# pump_system.net
KiCad netlist of a schematic drawn in EasyEDA
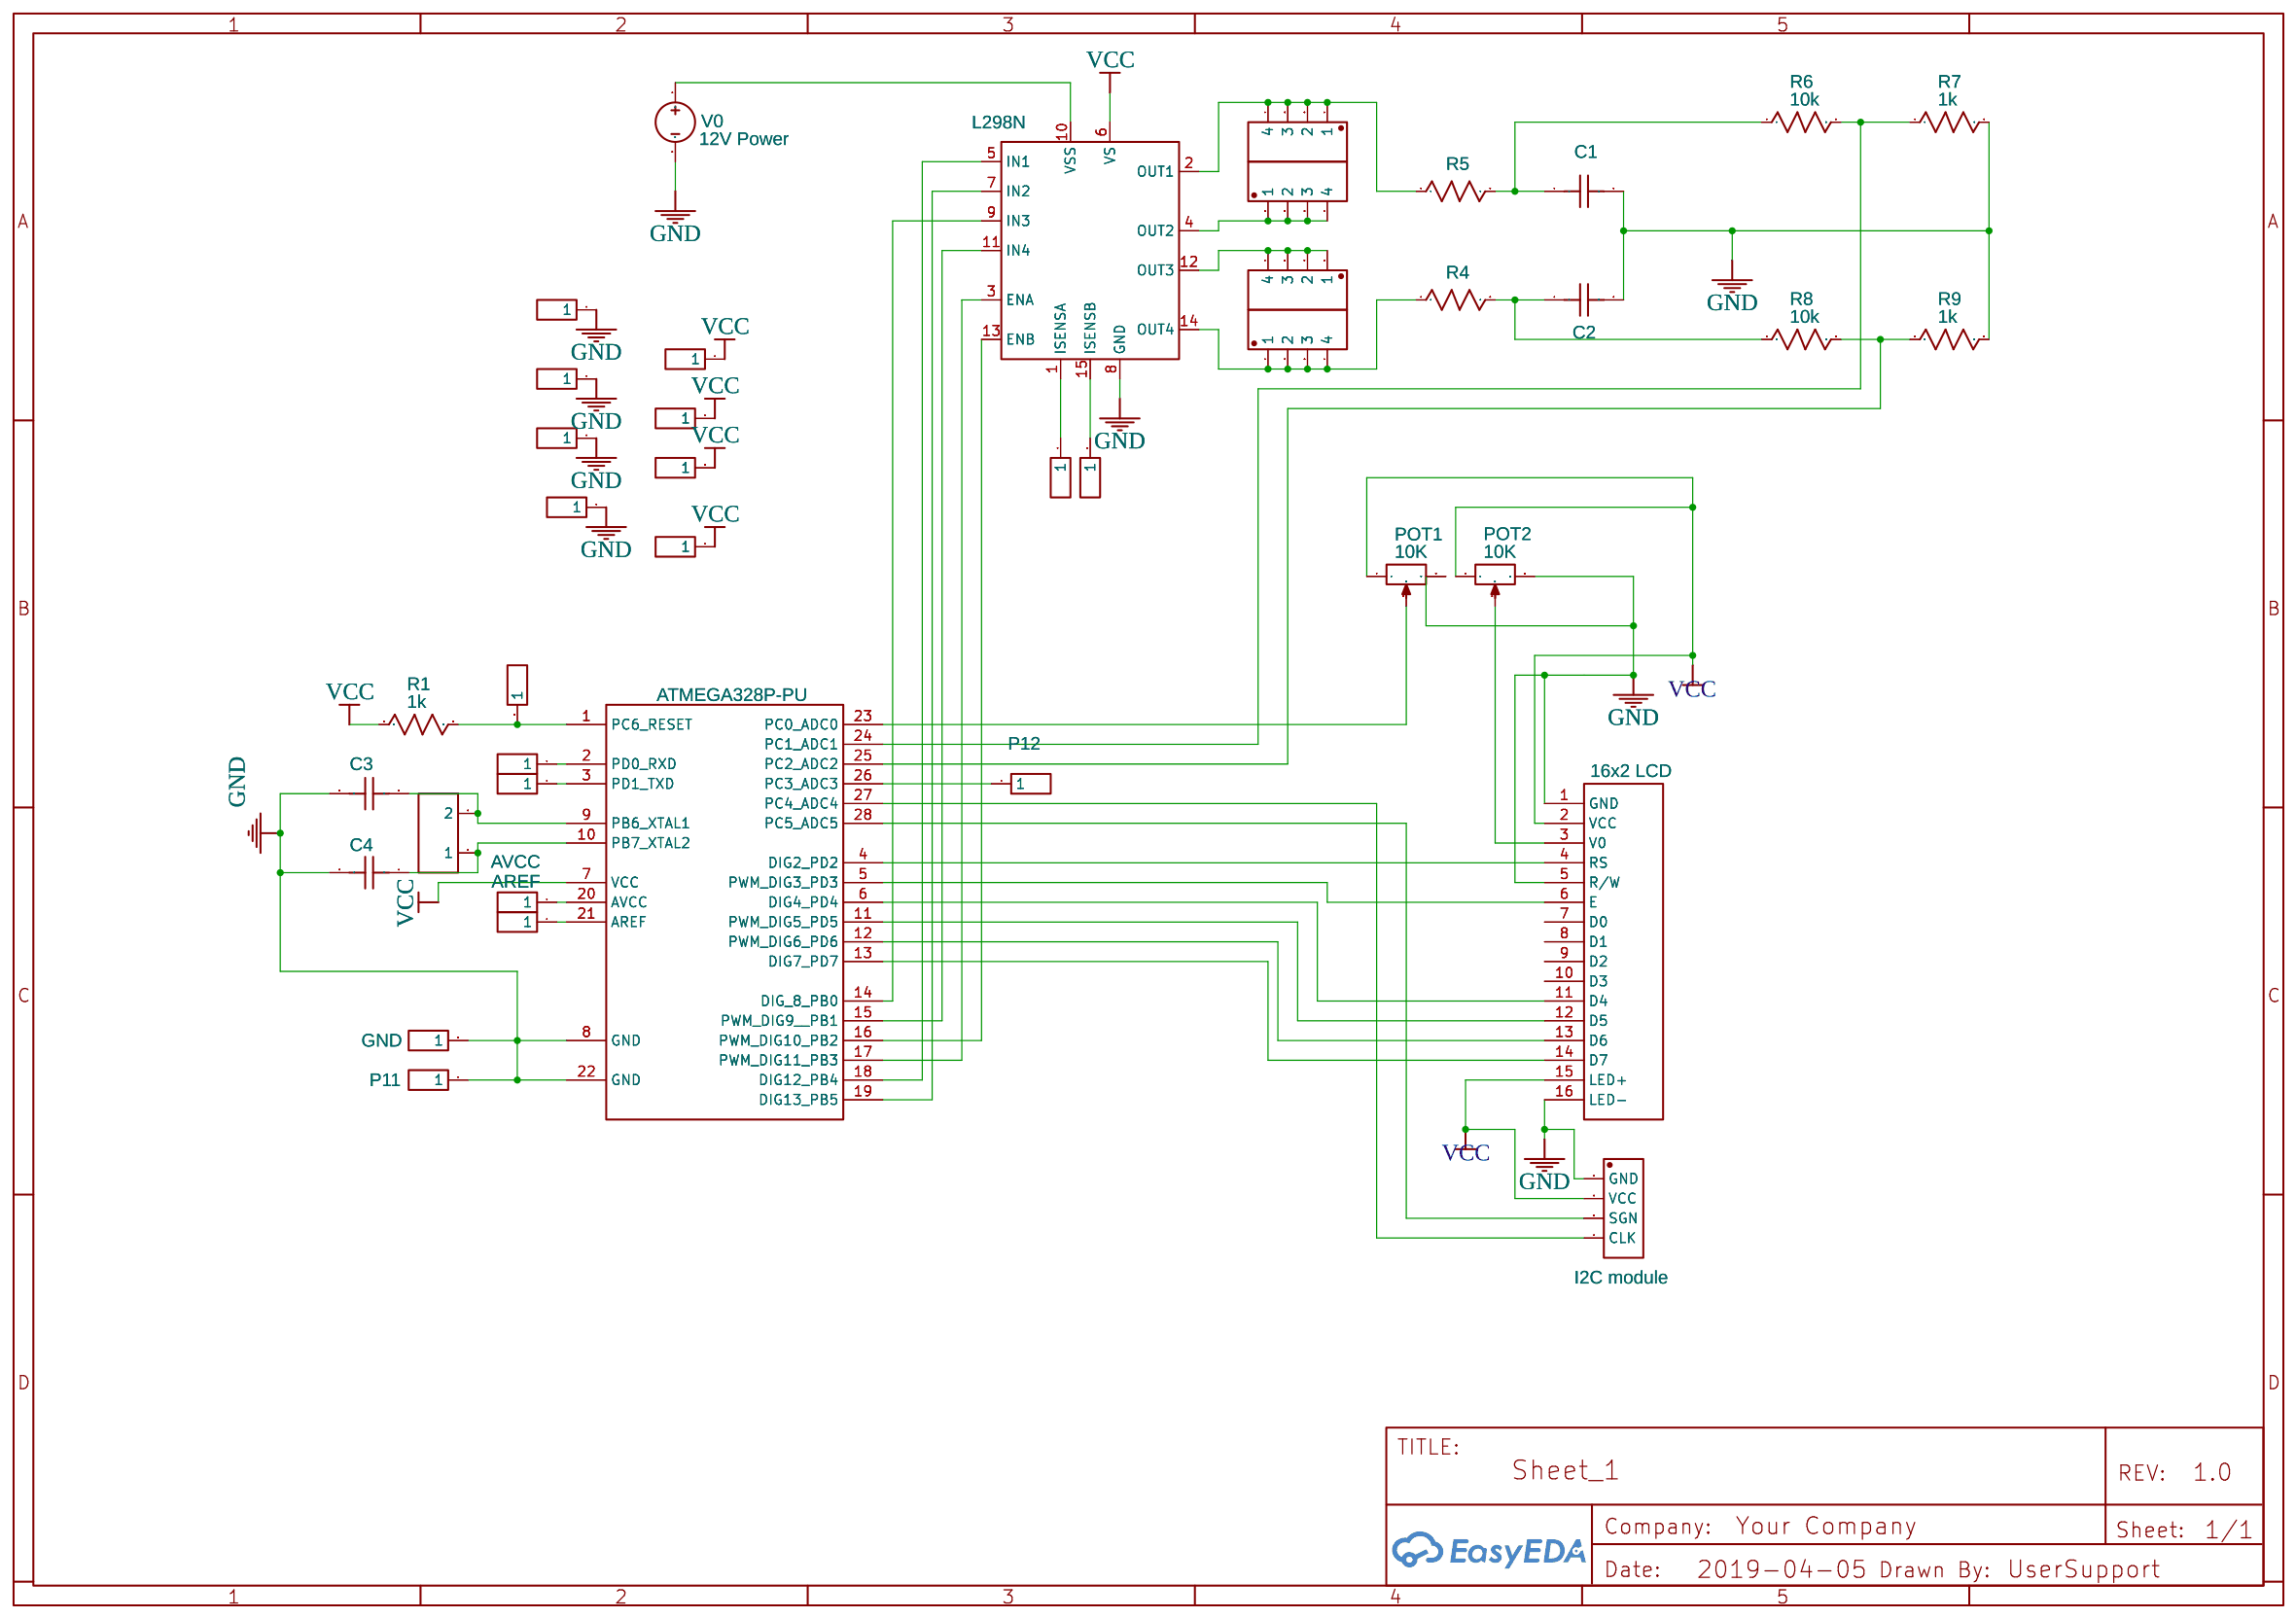
[diagram p0: schematic sheet]

(export (version "E")
  (design (tool "Eeschema 10.0.6"))
  (components
    (comp (ref "AREF")
      (value "Header-Male-2.54_1x1")
      (fields (field (name "BOM_Supplier Part") "C81276"))
      (libsource (lib "") (part "Unknown_260_460"))
    )
    (comp (ref "AVCC")
      (value "Header-Male-2.54_1x1")
      (fields (field (name "BOM_Supplier Part") "C81276"))
      (libsource (lib "") (part "Unknown_260_450"))
    )
    (comp (ref "C1")
      (value "1u")
      (fields (field (name "BOM_Manufacturer Part") "?"))
      (libsource (lib "") (part "Cap_RAD-0.1_US"))
    )
    (comp (ref "C2")
      (value "1u")
      (fields (field (name "BOM_Manufacturer Part") "?"))
      (libsource (lib "") (part "Cap_RAD-0.1_US"))
    )
    (comp (ref "C3")
      (value "1u")
      (fields (field (name "BOM_Manufacturer Part") "?"))
      (libsource (lib "") (part "Cap_RAD-0.1_US_1"))
    )
    (comp (ref "C4")
      (value "1u")
      (fields (field (name "BOM_Manufacturer Part") "?"))
      (libsource (lib "") (part "Cap_RAD-0.1_US_1"))
    )
    (comp (ref "GND")
      (value "Header-Male-2.54_1x1")
      (fields (field (name "BOM_Supplier Part") "C81276"))
      (libsource (lib "") (part "Unknown_215_520"))
    )
    (comp (ref "H1")
      (value "I2C module")
      (fields
        (field (name "BOM_Manufacturer Part") "210S-1*4P L=11.6MMGold-plated black")
        (field (name "BOM_Supplier Part") "C124378")
      )
      (libsource (lib "") (part "Unknown_810_605"))
    )
    (comp (ref "H2")
      (value "Header-Male-2.54_1x4")
      (fields
        (field (name "BOM_Manufacturer Part") "210S-1*4P L=11.6MMGold-plated black")
        (field (name "BOM_Supplier Part") "C124378")
      )
      (libsource (lib "") (part "Unknown_650_90"))
    )
    (comp (ref "H3")
      (value "Header-Male-2.54_1x4")
      (fields
        (field (name "BOM_Manufacturer Part") "210S-1*4P L=11.6MMGold-plated black")
        (field (name "BOM_Supplier Part") "C124378")
      )
      (libsource (lib "") (part "Unknown_650_60"))
    )
    (comp (ref "H4")
      (value "Header-Male-2.54_1x4")
      (fields
        (field (name "BOM_Manufacturer Part") "210S-1*4P L=11.6MMGold-plated black")
        (field (name "BOM_Supplier Part") "C124378")
      )
      (libsource (lib "") (part "Unknown_650_165"))
    )
    (comp (ref "H5")
      (value "Header-Male-2.54_1x4")
      (fields
        (field (name "BOM_Manufacturer Part") "210S-1*4P L=11.6MMGold-plated black")
        (field (name "BOM_Supplier Part") "C124378")
      )
      (libsource (lib "") (part "Unknown_650_135"))
    )
    (comp (ref "H6")
      (value "Header-Male-2.54_1x2")
      (fields (field (name "BOM_Manufacturer Part") "826629-2") (field (name "BOM_Supplier Part") "C86471"))
      (libsource (lib "") (part "Unknown_220_415"))
    )
    (comp (ref "L298N")
      (value "L298N Personal")
      (fields (field (name "BOM_Manufacturer Part") "L298N") (field (name "BOM_Supplier Part") "C19922"))
      (libsource (lib "") (part "Unknown_545_120"))
    )
    (comp (ref "P1")
      (value "Header-Male-2.54_1x1")
      (fields (field (name "BOM_Supplier Part") "C81276"))
      (libsource (lib "") (part "Unknown_280_150"))
    )
    (comp (ref "P2")
      (value "Header-Male-2.54_1x1")
      (fields (field (name "BOM_Supplier Part") "C81276"))
      (libsource (lib "") (part "Unknown_280_185"))
    )
    (comp (ref "P5")
      (value "Header-Male-2.54_1x1")
      (fields (field (name "BOM_Supplier Part") "C81276"))
      (libsource (lib "") (part "Unknown_280_215"))
    )
    (comp (ref "P7")
      (value "Header-Male-2.54_1x1")
      (fields (field (name "BOM_Supplier Part") "C81276"))
      (libsource (lib "") (part "Unknown_285_250"))
    )
    (comp (ref "P11")
      (value "Header-Male-2.54_1x1")
      (fields (field (name "BOM_Supplier Part") "C81276"))
      (libsource (lib "") (part "Unknown_215_540"))
    )
    (comp (ref "P12")
      (value "Header-Male-2.54_1x1")
      (fields (field (name "BOM_Supplier Part") "C81276"))
      (libsource (lib "") (part "Unknown_510_390"))
    )
    (comp (ref "P13")
      (value "Header-Male-2.54_1x1")
      (fields (field (name "BOM_Supplier Part") "C81276"))
      (libsource (lib "") (part "Unknown_545_230"))
    )
    (comp (ref "P14")
      (value "Header-Male-2.54_1x1")
      (fields (field (name "BOM_Supplier Part") "C81276"))
      (libsource (lib "") (part "Unknown_530_230"))
    )
    (comp (ref "P15")
      (value "Header-Male-2.54_1x1")
      (fields (field (name "BOM_Supplier Part") "C81276"))
      (libsource (lib "") (part "Unknown_340_270"))
    )
    (comp (ref "P16")
      (value "Header-Male-2.54_1x1")
      (fields (field (name "BOM_Supplier Part") "C81276"))
      (libsource (lib "") (part "Unknown_340_230"))
    )
    (comp (ref "P17")
      (value "Header-Male-2.54_1x1")
      (fields (field (name "BOM_Supplier Part") "C81276"))
      (libsource (lib "") (part "Unknown_340_205"))
    )
    (comp (ref "P18")
      (value "Header-Male-2.54_1x1")
      (fields (field (name "BOM_Supplier Part") "C81276"))
      (libsource (lib "") (part "Unknown_345_175"))
    )
    (comp (ref "POT1")
      (value "10K")
      (fields
        (field (name "BOM_Manufacturer Part") "Precision potentiometer100Ω")
        (field (name "BOM_Supplier Part") "C13649")
      )
      (libsource (lib "") (part "Precision potentiometer100Ω"))
    )
    (comp (ref "POT2")
      (value "10K")
      (fields
        (field (name "BOM_Manufacturer Part") "Precision potentiometer100Ω")
        (field (name "BOM_Supplier Part") "C13649")
      )
      (libsource (lib "") (part "Precision potentiometer100Ω"))
    )
    (comp (ref "R1")
      (value "1k")
      (fields (field (name "BOM_Manufacturer Part") "?"))
      (libsource (lib "") (part "Res_AXIAL-0.3(1/8W)_US"))
    )
    (comp (ref "R4")
      (value "1k")
      (fields (field (name "BOM_Manufacturer Part") "?"))
      (libsource (lib "") (part "Res_AXIAL-0.3(1/8W)_US"))
    )
    (comp (ref "R5")
      (value "1k")
      (fields (field (name "BOM_Manufacturer Part") "?"))
      (libsource (lib "") (part "Res_AXIAL-0.3(1/8W)_US"))
    )
    (comp (ref "R6")
      (value "10k")
      (fields (field (name "BOM_Manufacturer Part") "?"))
      (libsource (lib "") (part "Res_AXIAL-0.3(1/8W)_US"))
    )
    (comp (ref "R7")
      (value "1k")
      (fields (field (name "BOM_Manufacturer Part") "?"))
      (libsource (lib "") (part "Res_AXIAL-0.3(1/8W)_US"))
    )
    (comp (ref "R8")
      (value "10k")
      (fields (field (name "BOM_Manufacturer Part") "?"))
      (libsource (lib "") (part "Res_AXIAL-0.3(1/8W)_US"))
    )
    (comp (ref "R9")
      (value "1k")
      (fields (field (name "BOM_Manufacturer Part") "?"))
      (libsource (lib "") (part "Res_AXIAL-0.3(1/8W)_US"))
    )
    (comp (ref "RX")
      (value "Header-Male-2.54_1x1")
      (fields (field (name "BOM_Supplier Part") "C81276"))
      (libsource (lib "") (part "Unknown_260_380"))
    )
    (comp (ref "TX")
      (value "Header-Male-2.54_1x1")
      (fields (field (name "BOM_Supplier Part") "C81276"))
      (libsource (lib "") (part "Unknown_260_390"))
    )
    (comp (ref "U1")
      (value "ATMEGA328P-PU")
      (fields (field (name "BOM_Supplier Part") "C33901"))
      (libsource (lib "") (part "Unknown_360_455"))
    )
    (comp (ref "U4")
      (value "16x2 LCD")
      (fields (field (name "BOM_Manufacturer Part") "16x2 LCD (HD44780)"))
      (libsource (lib "") (part "Unknown_830_500"))
    )
    (comp (ref "V0")
      (value "12V Power")
      (fields (field (name "BOM_Manufacturer Part") "?"))
      (libsource (lib "") (part "Vsin"))
    )
    (comp (ref "VCC")
      (value "PC6 RESET")
      (fields
        (field (name "BOM_Manufacturer Part") "Header-Male-2.54_1x1")
        (field (name "BOM_Supplier Part") "C81276")
      )
      (libsource (lib "") (part "Unknown_255_345"))
    )
  )
  (nets
    (net (code "1") (name "GND") (class "Default")
      (node (ref "C1") (pin "2") (pinfunction "2_2") (pintype "unspecified"))
      (node (ref "C2") (pin "2") (pinfunction "2_2") (pintype "unspecified"))
      (node (ref "C3") (pin "2") (pinfunction "2_2") (pintype "unspecified"))
      (node (ref "C4") (pin "2") (pinfunction "2_2") (pintype "unspecified"))
      (node (ref "GND") (pin "1") (pinfunction "1_1") (pintype "input"))
      (node (ref "H1") (pin "1") (pinfunction "GND_1") (pintype "unspecified"))
      (node (ref "L298N") (pin "8") (pinfunction "GND_8") (pintype "unspecified"))
      (node (ref "P1") (pin "1") (pinfunction "1_1") (pintype "input"))
      (node (ref "P11") (pin "1") (pinfunction "1_1") (pintype "input"))
      (node (ref "P2") (pin "1") (pinfunction "1_1") (pintype "input"))
      (node (ref "P5") (pin "1") (pinfunction "1_1") (pintype "input"))
      (node (ref "P7") (pin "1") (pinfunction "1_1") (pintype "input"))
      (node (ref "POT1") (pin "3") (pinfunction "3_3") (pintype "input"))
      (node (ref "POT2") (pin "3") (pinfunction "3_3") (pintype "input"))
      (node (ref "R7") (pin "2") (pinfunction "2_2") (pintype "unspecified"))
      (node (ref "R9") (pin "2") (pinfunction "2_2") (pintype "unspecified"))
      (node (ref "U1") (pin "22") (pinfunction "GND_22") (pintype "passive"))
      (node (ref "U1") (pin "8") (pinfunction "GND_8") (pintype "passive"))
      (node (ref "U4") (pin "1") (pinfunction "GND_1") (pintype "unspecified"))
      (node (ref "U4") (pin "16") (pinfunction "LED-_16") (pintype "unspecified"))
      (node (ref "U4") (pin "5") (pinfunction "R/W_5") (pintype "unspecified"))
      (node (ref "V0") (pin "2") (pinfunction "2_2") (pintype "unspecified"))
    )
    (net (code "2") (name "Net-(C1-Pad1)") (class "Default")
      (node (ref "C1") (pin "1") (pinfunction "1_1") (pintype "unspecified"))
      (node (ref "R5") (pin "2") (pinfunction "2_2") (pintype "unspecified"))
      (node (ref "R6") (pin "1") (pinfunction "1_1") (pintype "unspecified"))
    )
    (net (code "3") (name "Net-(C2-Pad1)") (class "Default")
      (node (ref "C2") (pin "1") (pinfunction "1_1") (pintype "unspecified"))
      (node (ref "R4") (pin "2") (pinfunction "2_2") (pintype "unspecified"))
      (node (ref "R8") (pin "1") (pinfunction "1_1") (pintype "unspecified"))
    )
    (net (code "4") (name "Net-(H1-CLK)") (class "Default")
      (node (ref "H1") (pin "4") (pinfunction "CLK_4") (pintype "unspecified"))
      (node (ref "U1") (pin "27") (pinfunction "PC4_ADC4_27") (pintype "bidirectional"))
    )
    (net (code "5") (name "Net-(H1-SGN)") (class "Default")
      (node (ref "H1") (pin "3") (pinfunction "SGN_3") (pintype "unspecified"))
      (node (ref "U1") (pin "28") (pinfunction "PC5_ADC5_28") (pintype "bidirectional"))
    )
    (net (code "6") (name "Net-(L298N-ENA)") (class "Default")
      (node (ref "L298N") (pin "3") (pinfunction "ENA_3") (pintype "unspecified"))
      (node (ref "U1") (pin "17") (pinfunction "PWM_DIG11_PB3_17") (pintype "bidirectional"))
    )
    (net (code "7") (name "Net-(L298N-ENB)") (class "Default")
      (node (ref "L298N") (pin "13") (pinfunction "ENB_13") (pintype "unspecified"))
      (node (ref "U1") (pin "16") (pinfunction "PWM_DIG10_PB2_16") (pintype "bidirectional"))
    )
    (net (code "8") (name "Net-(L298N-IN1)") (class "Default")
      (node (ref "L298N") (pin "5") (pinfunction "IN1_5") (pintype "unspecified"))
      (node (ref "U1") (pin "18") (pinfunction "DIG12_PB4_18") (pintype "bidirectional"))
    )
    (net (code "9") (name "Net-(L298N-IN2)") (class "Default")
      (node (ref "L298N") (pin "7") (pinfunction "IN2_7") (pintype "unspecified"))
      (node (ref "U1") (pin "19") (pinfunction "DIG13_PB5_19") (pintype "bidirectional"))
    )
    (net (code "10") (name "Net-(L298N-IN3)") (class "Default")
      (node (ref "L298N") (pin "9") (pinfunction "IN3_9") (pintype "unspecified"))
      (node (ref "U1") (pin "14") (pinfunction "DIG_8_PB0_14") (pintype "bidirectional"))
    )
    (net (code "11") (name "Net-(L298N-IN4)") (class "Default")
      (node (ref "L298N") (pin "11") (pinfunction "IN4_11") (pintype "unspecified"))
      (node (ref "U1") (pin "15") (pinfunction "PWM_DIG9__PB1_15") (pintype "bidirectional"))
    )
    (net (code "12") (name "Net-(L298N-ISENSA)") (class "Default")
      (node (ref "L298N") (pin "1") (pinfunction "ISENSA_1") (pintype "unspecified"))
      (node (ref "P14") (pin "1") (pinfunction "1_1") (pintype "input"))
    )
    (net (code "13") (name "Net-(L298N-ISENSB)") (class "Default")
      (node (ref "L298N") (pin "15") (pinfunction "ISENSB_15") (pintype "unspecified"))
      (node (ref "P13") (pin "1") (pinfunction "1_1") (pintype "input"))
    )
    (net (code "14") (name "Net-(L298N-OUT1)") (class "Default")
      (node (ref "H3") (pin "1") (pinfunction "1_1") (pintype "unspecified"))
      (node (ref "H3") (pin "2") (pinfunction "2_2") (pintype "unspecified"))
      (node (ref "H3") (pin "3") (pinfunction "3_3") (pintype "unspecified"))
      (node (ref "H3") (pin "4") (pinfunction "4_4") (pintype "unspecified"))
      (node (ref "L298N") (pin "2") (pinfunction "OUT1_2") (pintype "unspecified"))
      (node (ref "R5") (pin "1") (pinfunction "1_1") (pintype "unspecified"))
    )
    (net (code "15") (name "Net-(L298N-OUT2)") (class "Default")
      (node (ref "H2") (pin "1") (pinfunction "1_1") (pintype "unspecified"))
      (node (ref "H2") (pin "2") (pinfunction "2_2") (pintype "unspecified"))
      (node (ref "H2") (pin "3") (pinfunction "3_3") (pintype "unspecified"))
      (node (ref "H2") (pin "4") (pinfunction "4_4") (pintype "unspecified"))
      (node (ref "L298N") (pin "4") (pinfunction "OUT2_4") (pintype "unspecified"))
    )
    (net (code "16") (name "Net-(L298N-OUT3)") (class "Default")
      (node (ref "H5") (pin "1") (pinfunction "1_1") (pintype "unspecified"))
      (node (ref "H5") (pin "2") (pinfunction "2_2") (pintype "unspecified"))
      (node (ref "H5") (pin "3") (pinfunction "3_3") (pintype "unspecified"))
      (node (ref "H5") (pin "4") (pinfunction "4_4") (pintype "unspecified"))
      (node (ref "L298N") (pin "12") (pinfunction "OUT3_12") (pintype "unspecified"))
    )
    (net (code "17") (name "Net-(L298N-OUT4)") (class "Default")
      (node (ref "H4") (pin "1") (pinfunction "1_1") (pintype "unspecified"))
      (node (ref "H4") (pin "2") (pinfunction "2_2") (pintype "unspecified"))
      (node (ref "H4") (pin "3") (pinfunction "3_3") (pintype "unspecified"))
      (node (ref "H4") (pin "4") (pinfunction "4_4") (pintype "unspecified"))
      (node (ref "L298N") (pin "14") (pinfunction "OUT4_14") (pintype "unspecified"))
      (node (ref "R4") (pin "1") (pinfunction "1_1") (pintype "unspecified"))
    )
    (net (code "18") (name "Net-(L298N-VSS)") (class "Default")
      (node (ref "L298N") (pin "10") (pinfunction "VSS_10") (pintype "unspecified"))
      (node (ref "V0") (pin "1") (pinfunction "1_1") (pintype "unspecified"))
    )
    (net (code "19") (name "Net-(U1-AREF)") (class "Default")
      (node (ref "AREF") (pin "1") (pinfunction "1_1") (pintype "input"))
      (node (ref "U1") (pin "21") (pinfunction "AREF_21") (pintype "passive"))
    )
    (net (code "20") (name "Net-(U1-AVCC)") (class "Default")
      (node (ref "AVCC") (pin "1") (pinfunction "1_1") (pintype "input"))
      (node (ref "U1") (pin "20") (pinfunction "AVCC_20") (pintype "passive"))
    )
    (net (code "21") (name "Net-(U1-DIG2_PD2)") (class "Default")
      (node (ref "U1") (pin "4") (pinfunction "DIG2_PD2_4") (pintype "bidirectional"))
      (node (ref "U4") (pin "4") (pinfunction "RS_4") (pintype "unspecified"))
    )
    (net (code "22") (name "Net-(U1-DIG4_PD4)") (class "Default")
      (node (ref "U1") (pin "6") (pinfunction "DIG4_PD4_6") (pintype "bidirectional"))
      (node (ref "U4") (pin "11") (pinfunction "D4_11") (pintype "unspecified"))
    )
    (net (code "23") (name "Net-(U1-DIG7_PD7)") (class "Default")
      (node (ref "U1") (pin "13") (pinfunction "DIG7_PD7_13") (pintype "bidirectional"))
      (node (ref "U4") (pin "14") (pinfunction "D7_14") (pintype "unspecified"))
    )
    (net (code "24") (name "Net-(U1-PB6_XTAL1)") (class "Default")
      (node (ref "C3") (pin "1") (pinfunction "1_1") (pintype "unspecified"))
      (node (ref "H6") (pin "2") (pinfunction "2_2") (pintype "unspecified"))
      (node (ref "U1") (pin "9") (pinfunction "PB6_XTAL1_9") (pintype "bidirectional"))
    )
    (net (code "25") (name "Net-(U1-PB7_XTAL2)") (class "Default")
      (node (ref "C4") (pin "1") (pinfunction "1_1") (pintype "unspecified"))
      (node (ref "H6") (pin "1") (pinfunction "1_1") (pintype "unspecified"))
      (node (ref "U1") (pin "10") (pinfunction "PB7_XTAL2_10") (pintype "bidirectional"))
    )
    (net (code "26") (name "Net-(U1-PC0_ADC0)") (class "Default")
      (node (ref "POT1") (pin "2") (pinfunction "2_2") (pintype "input"))
      (node (ref "U1") (pin "23") (pinfunction "PC0_ADC0_23") (pintype "bidirectional"))
    )
    (net (code "27") (name "Net-(U1-PC1_ADC1)") (class "Default")
      (node (ref "R6") (pin "2") (pinfunction "2_2") (pintype "unspecified"))
      (node (ref "R7") (pin "1") (pinfunction "1_1") (pintype "unspecified"))
      (node (ref "U1") (pin "24") (pinfunction "PC1_ADC1_24") (pintype "bidirectional"))
    )
    (net (code "28") (name "Net-(U1-PC2_ADC2)") (class "Default")
      (node (ref "R8") (pin "2") (pinfunction "2_2") (pintype "unspecified"))
      (node (ref "R9") (pin "1") (pinfunction "1_1") (pintype "unspecified"))
      (node (ref "U1") (pin "25") (pinfunction "PC2_ADC2_25") (pintype "bidirectional"))
    )
    (net (code "29") (name "Net-(U1-PC3_ADC3)") (class "Default")
      (node (ref "P12") (pin "1") (pinfunction "1_1") (pintype "input"))
      (node (ref "U1") (pin "26") (pinfunction "PC3_ADC3_26") (pintype "bidirectional"))
    )
    (net (code "30") (name "Net-(U1-PC6_RESET)") (class "Default")
      (node (ref "R1") (pin "2") (pinfunction "2_2") (pintype "unspecified"))
      (node (ref "U1") (pin "1") (pinfunction "PC6_RESET_1") (pintype "bidirectional"))
      (node (ref "VCC") (pin "1") (pinfunction "1_1") (pintype "input"))
    )
    (net (code "31") (name "Net-(U1-PD0_RXD)") (class "Default")
      (node (ref "RX") (pin "1") (pinfunction "1_1") (pintype "input"))
      (node (ref "U1") (pin "2") (pinfunction "PD0_RXD_2") (pintype "bidirectional"))
    )
    (net (code "32") (name "Net-(U1-PD1_TXD)") (class "Default")
      (node (ref "TX") (pin "1") (pinfunction "1_1") (pintype "input"))
      (node (ref "U1") (pin "3") (pinfunction "PD1_TXD_3") (pintype "bidirectional"))
    )
    (net (code "33") (name "Net-(U1-PWM_DIG3_PD3)") (class "Default")
      (node (ref "U1") (pin "5") (pinfunction "PWM_DIG3_PD3_5") (pintype "bidirectional"))
      (node (ref "U4") (pin "6") (pinfunction "E_6") (pintype "unspecified"))
    )
    (net (code "34") (name "Net-(U1-PWM_DIG5_PD5)") (class "Default")
      (node (ref "U1") (pin "11") (pinfunction "PWM_DIG5_PD5_11") (pintype "bidirectional"))
      (node (ref "U4") (pin "12") (pinfunction "D5_12") (pintype "unspecified"))
    )
    (net (code "35") (name "Net-(U1-PWM_DIG6_PD6)") (class "Default")
      (node (ref "U1") (pin "12") (pinfunction "PWM_DIG6_PD6_12") (pintype "bidirectional"))
      (node (ref "U4") (pin "13") (pinfunction "D6_13") (pintype "unspecified"))
    )
    (net (code "36") (name "Net-(U4-V0)") (class "Default")
      (node (ref "POT2") (pin "2") (pinfunction "2_2") (pintype "input"))
      (node (ref "U4") (pin "3") (pinfunction "V0_3") (pintype "unspecified"))
    )
    (net (code "37") (name "VCC") (class "Default")
      (node (ref "H1") (pin "2") (pinfunction "VCC_2") (pintype "unspecified"))
      (node (ref "L298N") (pin "6") (pinfunction "VS_6") (pintype "unspecified"))
      (node (ref "P15") (pin "1") (pinfunction "1_1") (pintype "input"))
      (node (ref "P16") (pin "1") (pinfunction "1_1") (pintype "input"))
      (node (ref "P17") (pin "1") (pinfunction "1_1") (pintype "input"))
      (node (ref "P18") (pin "1") (pinfunction "1_1") (pintype "input"))
      (node (ref "POT1") (pin "1") (pinfunction "1_1") (pintype "input"))
      (node (ref "POT2") (pin "1") (pinfunction "1_1") (pintype "input"))
      (node (ref "R1") (pin "1") (pinfunction "1_1") (pintype "unspecified"))
      (node (ref "U1") (pin "7") (pinfunction "VCC_7") (pintype "passive"))
      (node (ref "U4") (pin "15") (pinfunction "LED+_15") (pintype "unspecified"))
      (node (ref "U4") (pin "2") (pinfunction "VCC_2") (pintype "unspecified"))
    )
    (net (code "38") (name "unconnected-(U4-D0-Pad7)") (class "Default")
      (node (ref "U4") (pin "7") (pinfunction "D0_7") (pintype "unspecified"))
    )
    (net (code "39") (name "unconnected-(U4-D1-Pad8)") (class "Default")
      (node (ref "U4") (pin "8") (pinfunction "D1_8") (pintype "unspecified"))
    )
    (net (code "40") (name "unconnected-(U4-D2-Pad9)") (class "Default")
      (node (ref "U4") (pin "9") (pinfunction "D2_9") (pintype "unspecified"))
    )
    (net (code "41") (name "unconnected-(U4-D3-Pad10)") (class "Default")
      (node (ref "U4") (pin "10") (pinfunction "D3_10") (pintype "unspecified"))
    )
  )
)
